# AnalogBreakout.net
KiCad netlist of a schematic drawn in Altium Designer
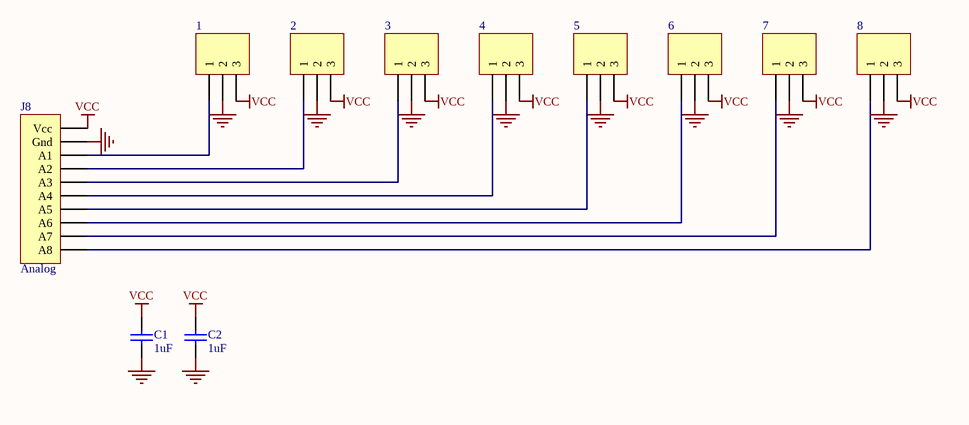
[diagram p0: AnalogBreakout.SchDoc]

(export (version "E")
  (design (tool "Eeschema 10.0.6"))
  (components
    (comp (ref "C1")
      (value "1uF")
      (footprint "CAPPR2.5-6.3x7")
      (description "Capacitor")
      (fields (field (name "Comment") "Cap") (field (name "PUBLISHER") "Altium Limited"))
      (libsource (lib "Miscellaneous Devices") (part "Cap"))
    )
    (comp (ref "C2")
      (value "1uF")
      (footprint "Cap SMD 1210")
      (description "Capacitor")
      (fields (field (name "Comment") "Cap") (field (name "PUBLISHER") "Altium Limited"))
      (libsource (lib "Custom") (part "Cap"))
    )
    (comp (ref "J8")
      (value "Analog")
      (footprint "0.1 SIP 10 PIN")
      (description "Header, 10-Pin")
      (fields (field (name "PUBLISHER") "Altium Limited"))
      (libsource (lib "Miscellaneous Connectors") (part "Header 10"))
    )
    (comp (ref "P1")
      (value "1")
      (footprint "HDR1X3")
      (description "Header, 3-Pin")
      (fields (field (name "PUBLISHER") "Altium Limited"))
      (libsource (lib "Miscellaneous Connectors") (part "Header 3"))
    )
    (comp (ref "P2")
      (value "2")
      (footprint "HDR1X3")
      (description "Header, 3-Pin")
      (fields (field (name "PUBLISHER") "Altium Limited"))
      (libsource (lib "Miscellaneous Connectors") (part "Header 3"))
    )
    (comp (ref "P3")
      (value "3")
      (footprint "HDR1X3")
      (description "Header, 3-Pin")
      (fields (field (name "PUBLISHER") "Altium Limited"))
      (libsource (lib "Miscellaneous Connectors") (part "Header 3"))
    )
    (comp (ref "P4")
      (value "4")
      (footprint "HDR1X3")
      (description "Header, 3-Pin")
      (fields (field (name "PUBLISHER") "Altium Limited"))
      (libsource (lib "Miscellaneous Connectors") (part "Header 3"))
    )
    (comp (ref "P5")
      (value "5")
      (footprint "HDR1X3")
      (description "Header, 3-Pin")
      (fields (field (name "PUBLISHER") "Altium Limited"))
      (libsource (lib "Miscellaneous Connectors") (part "Header 3"))
    )
    (comp (ref "P6")
      (value "6")
      (footprint "HDR1X3")
      (description "Header, 3-Pin")
      (fields (field (name "PUBLISHER") "Altium Limited"))
      (libsource (lib "Miscellaneous Connectors") (part "Header 3"))
    )
    (comp (ref "P7")
      (value "7")
      (footprint "HDR1X3")
      (description "Header, 3-Pin")
      (fields (field (name "PUBLISHER") "Altium Limited"))
      (libsource (lib "Miscellaneous Connectors") (part "Header 3"))
    )
    (comp (ref "P8")
      (value "8")
      (footprint "HDR1X3")
      (description "Header, 3-Pin")
      (fields (field (name "PUBLISHER") "Altium Limited"))
      (libsource (lib "Miscellaneous Connectors") (part "Header 3"))
    )
  )
  (nets
    (net (code "1") (name "GND") (class "Default")
      (node (ref "C1") (pin "2") (pinfunction "2_2") (pintype "passive"))
      (node (ref "C2") (pin "1") (pinfunction "1_1") (pintype "passive"))
      (node (ref "J8") (pin "2") (pinfunction "Gnd_2") (pintype "passive"))
      (node (ref "P1") (pin "2") (pinfunction "2_2") (pintype "passive"))
      (node (ref "P2") (pin "2") (pinfunction "2_2") (pintype "passive"))
      (node (ref "P3") (pin "2") (pinfunction "2_2") (pintype "passive"))
      (node (ref "P4") (pin "2") (pinfunction "2_2") (pintype "passive"))
      (node (ref "P5") (pin "2") (pinfunction "2_2") (pintype "passive"))
      (node (ref "P6") (pin "2") (pinfunction "2_2") (pintype "passive"))
      (node (ref "P7") (pin "2") (pinfunction "2_2") (pintype "passive"))
      (node (ref "P8") (pin "2") (pinfunction "2_2") (pintype "passive"))
    )
    (net (code "2") (name "Net-(J8-A1)") (class "Default")
      (node (ref "J8") (pin "3") (pinfunction "A1_3") (pintype "passive"))
      (node (ref "P1") (pin "1") (pinfunction "1_1") (pintype "passive"))
    )
    (net (code "3") (name "Net-(J8-A2)") (class "Default")
      (node (ref "J8") (pin "4") (pinfunction "A2_4") (pintype "passive"))
      (node (ref "P2") (pin "1") (pinfunction "1_1") (pintype "passive"))
    )
    (net (code "4") (name "Net-(J8-A3)") (class "Default")
      (node (ref "J8") (pin "5") (pinfunction "A3_5") (pintype "passive"))
      (node (ref "P3") (pin "1") (pinfunction "1_1") (pintype "passive"))
    )
    (net (code "5") (name "Net-(J8-A4)") (class "Default")
      (node (ref "J8") (pin "6") (pinfunction "A4_6") (pintype "passive"))
      (node (ref "P4") (pin "1") (pinfunction "1_1") (pintype "passive"))
    )
    (net (code "6") (name "Net-(J8-A5)") (class "Default")
      (node (ref "J8") (pin "7") (pinfunction "A5_7") (pintype "passive"))
      (node (ref "P5") (pin "1") (pinfunction "1_1") (pintype "passive"))
    )
    (net (code "7") (name "Net-(J8-A6)") (class "Default")
      (node (ref "J8") (pin "8") (pinfunction "A6_8") (pintype "passive"))
      (node (ref "P6") (pin "1") (pinfunction "1_1") (pintype "passive"))
    )
    (net (code "8") (name "Net-(J8-A7)") (class "Default")
      (node (ref "J8") (pin "9") (pinfunction "A7_9") (pintype "passive"))
      (node (ref "P7") (pin "1") (pinfunction "1_1") (pintype "passive"))
    )
    (net (code "9") (name "Net-(J8-A8)") (class "Default")
      (node (ref "J8") (pin "10") (pinfunction "A8_10") (pintype "passive"))
      (node (ref "P8") (pin "1") (pinfunction "1_1") (pintype "passive"))
    )
    (net (code "10") (name "VCC") (class "Default")
      (node (ref "C1") (pin "1") (pinfunction "1_1") (pintype "passive"))
      (node (ref "C2") (pin "2") (pinfunction "2_2") (pintype "passive"))
      (node (ref "J8") (pin "1") (pinfunction "Vcc_1") (pintype "passive"))
      (node (ref "P1") (pin "3") (pinfunction "3_3") (pintype "passive"))
      (node (ref "P2") (pin "3") (pinfunction "3_3") (pintype "passive"))
      (node (ref "P3") (pin "3") (pinfunction "3_3") (pintype "passive"))
      (node (ref "P4") (pin "3") (pinfunction "3_3") (pintype "passive"))
      (node (ref "P5") (pin "3") (pinfunction "3_3") (pintype "passive"))
      (node (ref "P6") (pin "3") (pinfunction "3_3") (pintype "passive"))
      (node (ref "P7") (pin "3") (pinfunction "3_3") (pintype "passive"))
      (node (ref "P8") (pin "3") (pinfunction "3_3") (pintype "passive"))
    )
  )
)
